# ChassisCab-samd21g.net
KiCad netlist of a schematic drawn in EAGLE
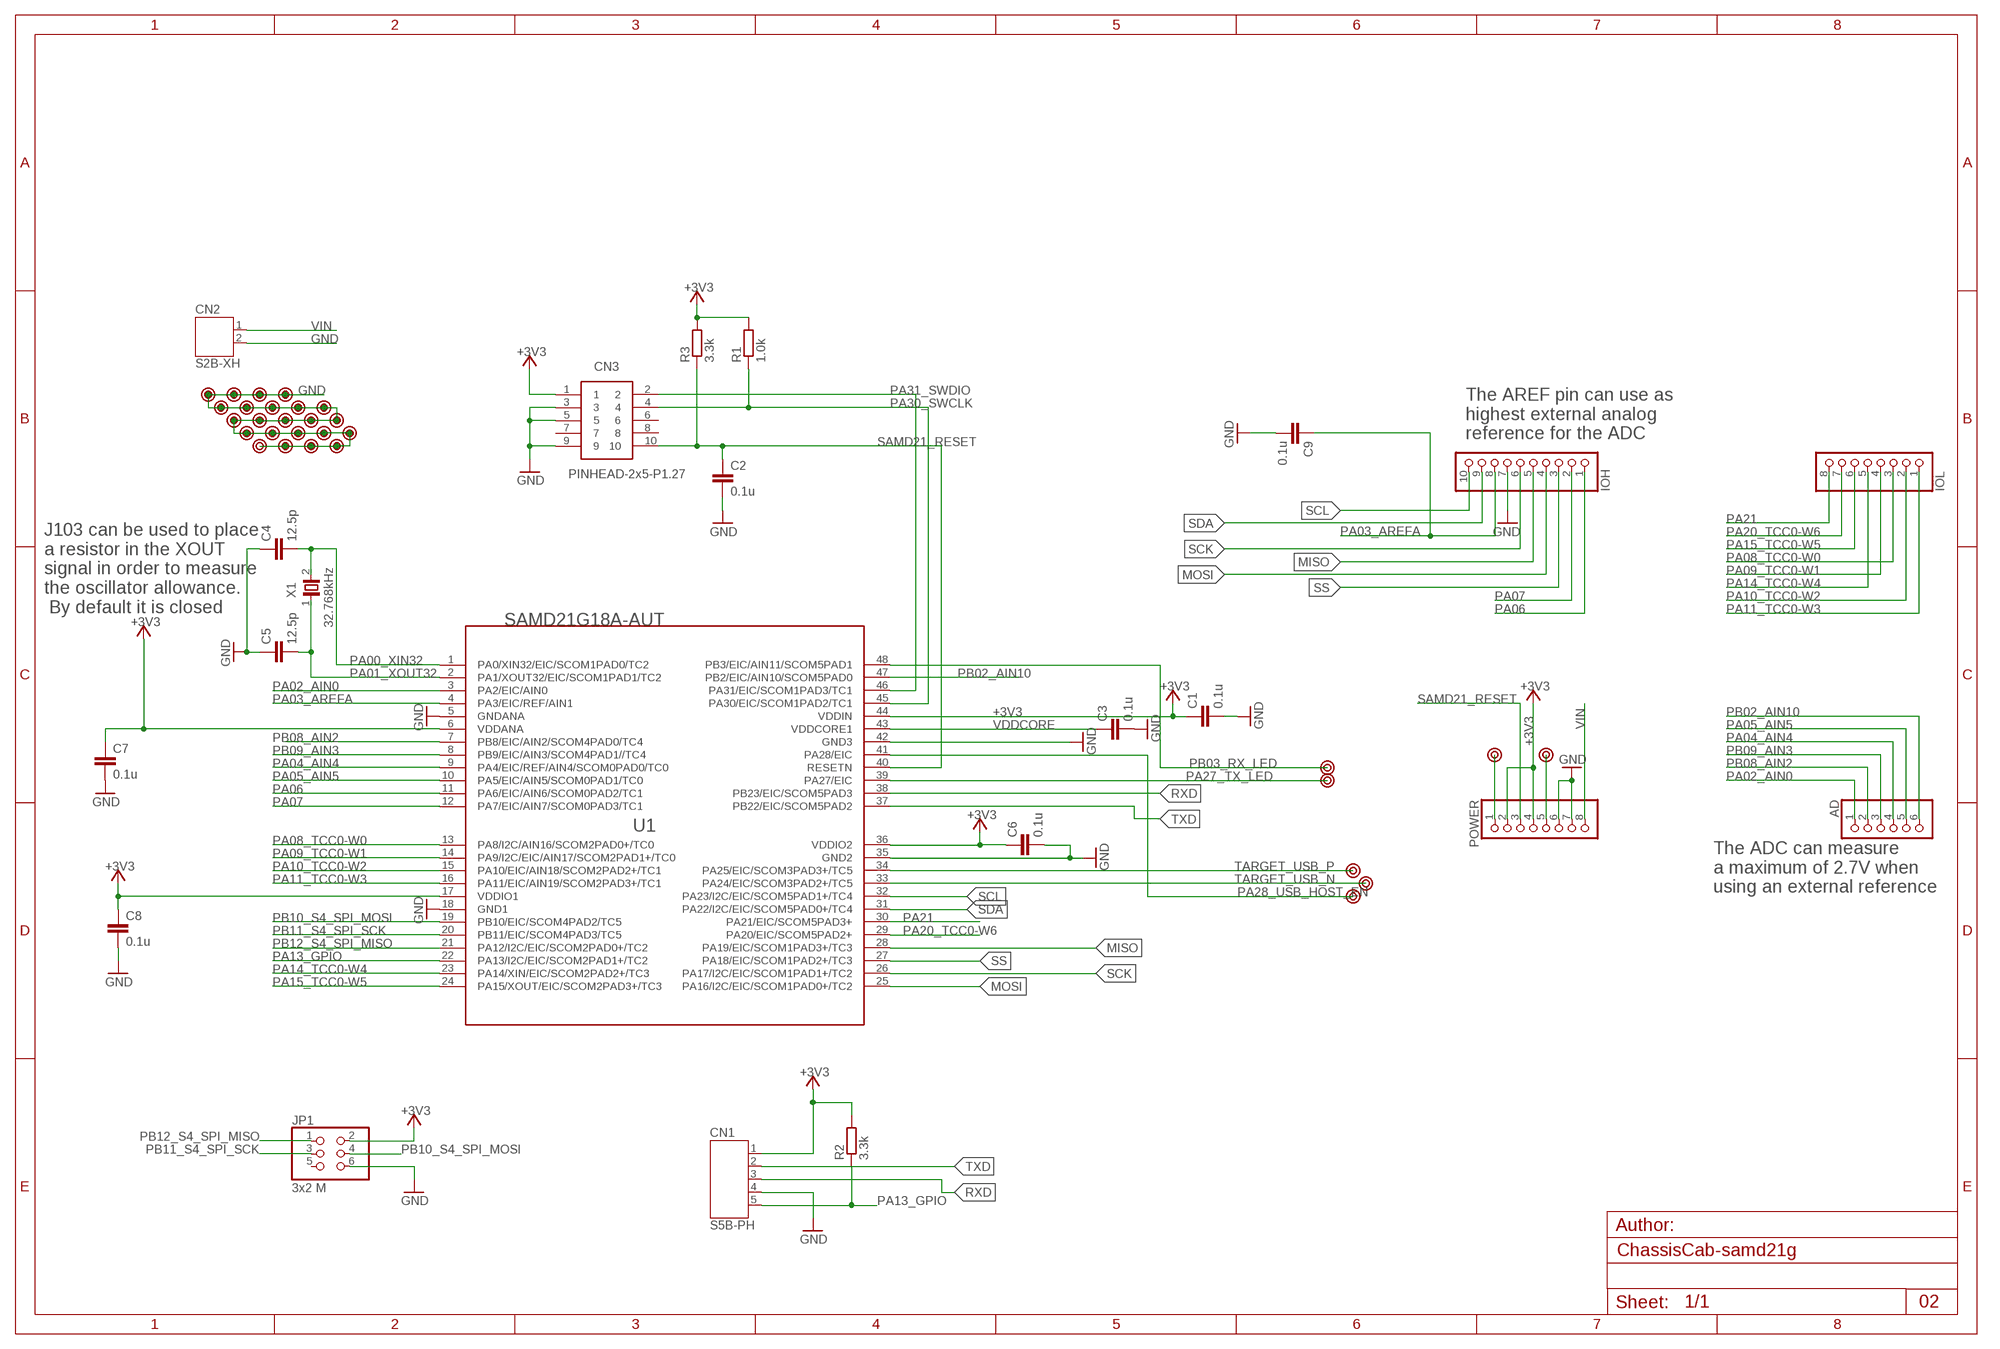
[diagram p0: schematic, sheet 1]

(export (version "E")
  (design (tool "Eeschema 10.0.6"))
  (components
    (comp (ref "AD")
      (value "6x1F-H8.5")
      (footprint "eagle-import:1X06")
      (libsource (lib "eagle-import") (part "PINHD-1X6"))
    )
    (comp (ref "C1")
      (value "0.1u")
      (footprint "eagle-import:C0603")
      (libsource (lib "eagle-import") (part "C-EUC0603"))
    )
    (comp (ref "C2")
      (value "0.1u")
      (footprint "eagle-import:C0603")
      (libsource (lib "eagle-import") (part "C-EUC0603"))
    )
    (comp (ref "C3")
      (value "0.1u")
      (footprint "eagle-import:C0603")
      (libsource (lib "eagle-import") (part "C-EUC0603"))
    )
    (comp (ref "C4")
      (value "12.5p")
      (footprint "eagle-import:C0603")
      (libsource (lib "eagle-import") (part "C-EUC0603"))
    )
    (comp (ref "C5")
      (value "12.5p")
      (footprint "eagle-import:C0603")
      (libsource (lib "eagle-import") (part "C-EUC0603"))
    )
    (comp (ref "C6")
      (value "0.1u")
      (footprint "eagle-import:C0603")
      (libsource (lib "eagle-import") (part "C-EUC0603"))
    )
    (comp (ref "C7")
      (value "0.1u")
      (footprint "eagle-import:C0603")
      (libsource (lib "eagle-import") (part "C-EUC0603"))
    )
    (comp (ref "C8")
      (value "0.1u")
      (footprint "eagle-import:C0603")
      (libsource (lib "eagle-import") (part "C-EUC0603"))
    )
    (comp (ref "C9")
      (value "0.1u")
      (footprint "eagle-import:C0603")
      (libsource (lib "eagle-import") (part "C-EUC0603"))
    )
    (comp (ref "CN1")
      (value "S5B-PH")
      (footprint "eagle-import:S5B-PH")
      (libsource (lib "eagle-import") (part "S5B-PH"))
    )
    (comp (ref "CN2")
      (value "S2B-XH")
      (footprint "eagle-import:S2B-XH")
      (libsource (lib "eagle-import") (part "S2B-XH"))
    )
    (comp (ref "CN3")
      (value "PINHEAD-2x5-P1.27")
      (footprint "eagle-import:SHF-105-01-X-D-SM")
      (libsource (lib "eagle-import") (part "SHF-105-01-X-D-SM"))
    )
    (comp (ref "IOH")
      (value "10x1F-H8.5")
      (footprint "eagle-import:1X10")
      (libsource (lib "eagle-import") (part "PINHD-1X10_ARD"))
    )
    (comp (ref "IOL")
      (value "8x1F-H8.5")
      (footprint "eagle-import:1X08")
      (libsource (lib "eagle-import") (part "PINHD-1X8"))
    )
    (comp (ref "JP1")
      (value "3x2 M")
      (footprint "eagle-import:2X03")
      (libsource (lib "eagle-import") (part "PINHD-2X3"))
    )
    (comp (ref "POWER")
      (value "8x1F-H8.5")
      (footprint "eagle-import:1X08")
      (libsource (lib "eagle-import") (part "PINHD-1X8"))
    )
    (comp (ref "R1")
      (value "1.0k")
      (footprint "eagle-import:R0603")
      (libsource (lib "eagle-import") (part "R-EU_R0603"))
    )
    (comp (ref "R2")
      (value "3.3k")
      (footprint "eagle-import:R0603")
      (libsource (lib "eagle-import") (part "R-EU_R0603"))
    )
    (comp (ref "R3")
      (value "3.3k")
      (footprint "eagle-import:R0603")
      (libsource (lib "eagle-import") (part "R-EU_R0603"))
    )
    (comp (ref "U$1")
      (value "PAD")
      (footprint "eagle-import:PAD")
      (libsource (lib "eagle-import") (part "PAD"))
    )
    (comp (ref "U$2")
      (value "PAD")
      (footprint "eagle-import:PAD")
      (libsource (lib "eagle-import") (part "PAD"))
    )
    (comp (ref "U$3")
      (value "PAD")
      (footprint "eagle-import:PAD")
      (libsource (lib "eagle-import") (part "PAD"))
    )
    (comp (ref "U$4")
      (value "PAD")
      (footprint "eagle-import:PAD")
      (libsource (lib "eagle-import") (part "PAD"))
    )
    (comp (ref "U$6")
      (value "PAD")
      (footprint "eagle-import:PAD")
      (libsource (lib "eagle-import") (part "PAD"))
    )
    (comp (ref "U$7")
      (value "PAD")
      (footprint "eagle-import:PAD")
      (libsource (lib "eagle-import") (part "PAD"))
    )
    (comp (ref "U$8")
      (value "PAD")
      (footprint "eagle-import:PAD")
      (libsource (lib "eagle-import") (part "PAD"))
    )
    (comp (ref "U$9")
      (value "PAD")
      (footprint "eagle-import:PAD")
      (libsource (lib "eagle-import") (part "PAD"))
    )
    (comp (ref "U$10")
      (value "PAD")
      (footprint "eagle-import:PAD")
      (libsource (lib "eagle-import") (part "PAD"))
    )
    (comp (ref "U$11")
      (value "PAD")
      (footprint "eagle-import:PAD")
      (libsource (lib "eagle-import") (part "PAD"))
    )
    (comp (ref "U$12")
      (value "PAD")
      (footprint "eagle-import:PAD")
      (libsource (lib "eagle-import") (part "PAD"))
    )
    (comp (ref "U$13")
      (value "PAD")
      (footprint "eagle-import:PAD")
      (libsource (lib "eagle-import") (part "PAD"))
    )
    (comp (ref "U$14")
      (value "PAD")
      (footprint "eagle-import:PAD")
      (libsource (lib "eagle-import") (part "PAD"))
    )
    (comp (ref "U$15")
      (value "PAD")
      (footprint "eagle-import:PAD")
      (libsource (lib "eagle-import") (part "PAD"))
    )
    (comp (ref "U$16")
      (value "PAD")
      (footprint "eagle-import:PAD")
      (libsource (lib "eagle-import") (part "PAD"))
    )
    (comp (ref "U$17")
      (value "PAD")
      (footprint "eagle-import:PAD")
      (libsource (lib "eagle-import") (part "PAD"))
    )
    (comp (ref "U$18")
      (value "PAD")
      (footprint "eagle-import:PAD")
      (libsource (lib "eagle-import") (part "PAD"))
    )
    (comp (ref "U$19")
      (value "PAD")
      (footprint "eagle-import:PAD")
      (libsource (lib "eagle-import") (part "PAD"))
    )
    (comp (ref "U$20")
      (value "PAD")
      (footprint "eagle-import:PAD")
      (libsource (lib "eagle-import") (part "PAD"))
    )
    (comp (ref "U$21")
      (value "PAD")
      (footprint "eagle-import:PAD")
      (libsource (lib "eagle-import") (part "PAD"))
    )
    (comp (ref "U$22")
      (value "PAD")
      (footprint "eagle-import:PAD")
      (libsource (lib "eagle-import") (part "PAD"))
    )
    (comp (ref "U$23")
      (value "PAD")
      (footprint "eagle-import:PAD")
      (libsource (lib "eagle-import") (part "PAD"))
    )
    (comp (ref "U$24")
      (value "PAD")
      (footprint "eagle-import:PAD")
      (libsource (lib "eagle-import") (part "PAD"))
    )
    (comp (ref "U$25")
      (value "PAD")
      (footprint "eagle-import:PAD")
      (libsource (lib "eagle-import") (part "PAD"))
    )
    (comp (ref "U$26")
      (value "PAD")
      (footprint "eagle-import:PAD")
      (libsource (lib "eagle-import") (part "PAD"))
    )
    (comp (ref "U$27")
      (value "PAD")
      (footprint "eagle-import:PAD")
      (libsource (lib "eagle-import") (part "PAD"))
    )
    (comp (ref "U$28")
      (value "PAD")
      (footprint "eagle-import:PAD")
      (libsource (lib "eagle-import") (part "PAD"))
    )
    (comp (ref "U$29")
      (value "PAD")
      (footprint "eagle-import:PAD")
      (libsource (lib "eagle-import") (part "PAD"))
    )
    (comp (ref "U$30")
      (value "PAD")
      (footprint "eagle-import:PAD")
      (libsource (lib "eagle-import") (part "PAD"))
    )
    (comp (ref "U$31")
      (value "PAD")
      (footprint "eagle-import:PAD")
      (libsource (lib "eagle-import") (part "PAD"))
    )
    (comp (ref "U1")
      (value "SAMD21G18A-AUT")
      (footprint "eagle-import:TQFP48")
      (libsource (lib "eagle-import") (part "SAMD21G18A"))
    )
    (comp (ref "X1")
      (value "32.768kHz")
      (footprint "eagle-import:FC-135")
      (libsource (lib "eagle-import") (part "FC-135"))
    )
  )
  (nets
    (net (code "1") (name "+3V3") (class "Default")
      (node (ref "C1") (pin "1") (pinfunction "1_1") (pintype "passive"))
      (node (ref "C6") (pin "1") (pinfunction "1_1") (pintype "passive"))
      (node (ref "C7") (pin "1") (pinfunction "1_1") (pintype "passive"))
      (node (ref "C8") (pin "1") (pinfunction "1_1") (pintype "passive"))
      (node (ref "CN1") (pin "1") (pinfunction "1_1") (pintype "passive"))
      (node (ref "CN3") (pin "1") (pinfunction "1_1") (pintype "bidirectional"))
      (node (ref "JP1") (pin "2") (pinfunction "2_2") (pintype "passive"))
      (node (ref "POWER") (pin "2") (pinfunction "2_2") (pintype "passive"))
      (node (ref "POWER") (pin "4") (pinfunction "4_4") (pintype "passive"))
      (node (ref "R1") (pin "2") (pinfunction "2_2") (pintype "passive"))
      (node (ref "R2") (pin "2") (pinfunction "2_2") (pintype "passive"))
      (node (ref "R3") (pin "2") (pinfunction "2_2") (pintype "passive"))
      (node (ref "U1") (pin "17") (pinfunction "VDDIO1_17") (pintype "power_in"))
      (node (ref "U1") (pin "36") (pinfunction "VDDIO2_36") (pintype "power_in"))
      (node (ref "U1") (pin "44") (pinfunction "VDDIN_44") (pintype "power_in"))
      (node (ref "U1") (pin "6") (pinfunction "VDDANA_6") (pintype "power_in"))
    )
    (net (code "2") (name "/PA00_XIN32") (class "Default")
      (node (ref "C4") (pin "2") (pinfunction "2_2") (pintype "passive"))
      (node (ref "U1") (pin "1") (pinfunction "PA0/XIN32/EIC/SCOM1PAD0/TC2_1") (pintype "bidirectional"))
      (node (ref "X1") (pin "2") (pinfunction "2_2") (pintype "passive"))
    )
    (net (code "3") (name "/PA01_XOUT32") (class "Default")
      (node (ref "C5") (pin "2") (pinfunction "2_2") (pintype "passive"))
      (node (ref "U1") (pin "2") (pinfunction "PA1/XOUT32/EIC/SCOM1PAD1/TC2_2") (pintype "bidirectional"))
      (node (ref "X1") (pin "1") (pinfunction "1_1") (pintype "passive"))
    )
    (net (code "4") (name "/PA02_AIN0") (class "Default")
      (node (ref "AD") (pin "1") (pinfunction "1_1") (pintype "passive"))
      (node (ref "U1") (pin "3") (pinfunction "PA2/EIC/AIN0_3") (pintype "bidirectional"))
    )
    (net (code "5") (name "/PA03_AREFA") (class "Default")
      (node (ref "C9") (pin "1") (pinfunction "1_1") (pintype "passive"))
      (node (ref "IOH") (pin "8") (pinfunction "8_8") (pintype "passive"))
      (node (ref "U1") (pin "4") (pinfunction "PA3/EIC/REF/AIN1_4") (pintype "bidirectional"))
    )
    (net (code "6") (name "/PA04_AIN4") (class "Default")
      (node (ref "AD") (pin "4") (pinfunction "4_4") (pintype "passive"))
      (node (ref "U1") (pin "9") (pinfunction "PA4/EIC/REF/AIN4/SCOM0PAD0/TC0_9") (pintype "bidirectional"))
    )
    (net (code "7") (name "/PA05_AIN5") (class "Default")
      (node (ref "AD") (pin "5") (pinfunction "5_5") (pintype "passive"))
      (node (ref "U1") (pin "10") (pinfunction "PA5/EIC/AIN5/SCOM0PAD1/TC0_10") (pintype "bidirectional"))
    )
    (net (code "8") (name "/PA06") (class "Default")
      (node (ref "IOH") (pin "1") (pinfunction "1_1") (pintype "passive"))
      (node (ref "U1") (pin "11") (pinfunction "PA6/EIC/AIN6/SCOM0PAD2/TC1_11") (pintype "bidirectional"))
    )
    (net (code "9") (name "/PA07") (class "Default")
      (node (ref "IOH") (pin "2") (pinfunction "2_2") (pintype "passive"))
      (node (ref "U1") (pin "12") (pinfunction "PA7/EIC/AIN7/SCOM0PAD3/TC1_12") (pintype "bidirectional"))
    )
    (net (code "10") (name "/PA08_TCC0-W0") (class "Default")
      (node (ref "IOL") (pin "3") (pinfunction "3_3") (pintype "passive"))
      (node (ref "U1") (pin "13") (pinfunction "PA8/I2C/AIN16/SCOM2PAD0+/TC0_13") (pintype "bidirectional"))
    )
    (net (code "11") (name "/PA09_TCC0-W1") (class "Default")
      (node (ref "IOL") (pin "4") (pinfunction "4_4") (pintype "passive"))
      (node (ref "U1") (pin "14") (pinfunction "PA9/I2C/EIC/AIN17/SCOM2PAD1+/TC0_14") (pintype "bidirectional"))
    )
    (net (code "12") (name "/PA10_TCC0-W2") (class "Default")
      (node (ref "IOL") (pin "2") (pinfunction "2_2") (pintype "passive"))
      (node (ref "U1") (pin "15") (pinfunction "PA10/EIC/AIN18/SCOM2PAD2+/TC1_15") (pintype "bidirectional"))
    )
    (net (code "13") (name "/PA11_TCC0-W3") (class "Default")
      (node (ref "IOL") (pin "1") (pinfunction "1_1") (pintype "passive"))
      (node (ref "U1") (pin "16") (pinfunction "PA11/EIC/AIN19/SCOM2PAD3+/TC1_16") (pintype "bidirectional"))
    )
    (net (code "14") (name "/PA13_GPIO") (class "Default")
      (node (ref "CN1") (pin "5") (pinfunction "5_5") (pintype "passive"))
      (node (ref "R2") (pin "1") (pinfunction "1_1") (pintype "passive"))
      (node (ref "U1") (pin "22") (pinfunction "PA13/I2C/EIC/SCOM2PAD1+/TC2_22") (pintype "bidirectional"))
    )
    (net (code "15") (name "/PA14_TCC0-W4") (class "Default")
      (node (ref "IOL") (pin "5") (pinfunction "5_5") (pintype "passive"))
      (node (ref "U1") (pin "23") (pinfunction "PA14/XIN/EIC/SCOM2PAD2+/TC3_23") (pintype "bidirectional"))
    )
    (net (code "16") (name "/PA15_TCC0-W5") (class "Default")
      (node (ref "IOL") (pin "6") (pinfunction "6_6") (pintype "passive"))
      (node (ref "U1") (pin "24") (pinfunction "PA15/XOUT/EIC/SCOM2PAD3+/TC3_24") (pintype "bidirectional"))
    )
    (net (code "17") (name "/PA20_TCC0-W6") (class "Default")
      (node (ref "IOL") (pin "7") (pinfunction "7_7") (pintype "passive"))
      (node (ref "U1") (pin "29") (pinfunction "PA20/EIC/SCOM5PAD2+_29") (pintype "bidirectional"))
    )
    (net (code "18") (name "/PA21") (class "Default")
      (node (ref "IOL") (pin "8") (pinfunction "8_8") (pintype "passive"))
      (node (ref "U1") (pin "30") (pinfunction "PA21/EIC/SCOM5PAD3+_30") (pintype "bidirectional"))
    )
    (net (code "19") (name "/PA27_TX_LED") (class "Default")
      (node (ref "U$4") (pin "1") (pinfunction "1_1") (pintype "passive"))
      (node (ref "U1") (pin "39") (pinfunction "PA27/EIC_39") (pintype "bidirectional"))
    )
    (net (code "20") (name "/PA28_USB_HOST_EN") (class "Default")
      (node (ref "U$3") (pin "1") (pinfunction "1_1") (pintype "passive"))
      (node (ref "U1") (pin "41") (pinfunction "PA28/EIC_41") (pintype "bidirectional"))
    )
    (net (code "21") (name "/PA30_SWCLK") (class "Default")
      (node (ref "CN3") (pin "4") (pinfunction "4_4") (pintype "bidirectional"))
      (node (ref "R1") (pin "1") (pinfunction "1_1") (pintype "passive"))
      (node (ref "U1") (pin "45") (pinfunction "PA30/EIC/SCOM1PAD2/TC1_45") (pintype "bidirectional"))
    )
    (net (code "22") (name "/PA31_SWDIO") (class "Default")
      (node (ref "CN3") (pin "2") (pinfunction "2_2") (pintype "bidirectional"))
      (node (ref "U1") (pin "46") (pinfunction "PA31/EIC/SCOM1PAD3/TC1_46") (pintype "bidirectional"))
    )
    (net (code "23") (name "/PB02_AIN10") (class "Default")
      (node (ref "AD") (pin "6") (pinfunction "6_6") (pintype "passive"))
      (node (ref "U1") (pin "47") (pinfunction "PB2/EIC/AIN10/SCOM5PAD0_47") (pintype "bidirectional"))
    )
    (net (code "24") (name "/PB03_RX_LED") (class "Default")
      (node (ref "U$1") (pin "1") (pinfunction "1_1") (pintype "passive"))
      (node (ref "U1") (pin "48") (pinfunction "PB3/EIC/AIN11/SCOM5PAD1_48") (pintype "bidirectional"))
    )
    (net (code "25") (name "/PB08_AIN2") (class "Default")
      (node (ref "AD") (pin "2") (pinfunction "2_2") (pintype "passive"))
      (node (ref "U1") (pin "7") (pinfunction "PB8/EIC/AIN2/SCOM4PAD0/TC4_7") (pintype "bidirectional"))
    )
    (net (code "26") (name "/PB09_AIN3") (class "Default")
      (node (ref "AD") (pin "3") (pinfunction "3_3") (pintype "passive"))
      (node (ref "U1") (pin "8") (pinfunction "PB9/EIC/AIN3/SCOM4PAD1//TC4_8") (pintype "bidirectional"))
    )
    (net (code "27") (name "/PB10_S4_SPI_MOSI") (class "Default")
      (node (ref "JP1") (pin "4") (pinfunction "4_4") (pintype "passive"))
      (node (ref "U1") (pin "19") (pinfunction "PB10/EIC/SCOM4PAD2/TC5_19") (pintype "bidirectional"))
    )
    (net (code "28") (name "/PB11_S4_SPI_SCK") (class "Default")
      (node (ref "JP1") (pin "3") (pinfunction "3_3") (pintype "passive"))
      (node (ref "U1") (pin "20") (pinfunction "PB11/EIC/SCOM4PAD3/TC5_20") (pintype "bidirectional"))
    )
    (net (code "29") (name "/PB12_S4_SPI_MISO") (class "Default")
      (node (ref "JP1") (pin "1") (pinfunction "1_1") (pintype "passive"))
      (node (ref "U1") (pin "21") (pinfunction "PA12/I2C/EIC/SCOM2PAD0+/TC2_21") (pintype "bidirectional"))
    )
    (net (code "30") (name "/SAMD21_RESET") (class "Default")
      (node (ref "C2") (pin "1") (pinfunction "1_1") (pintype "passive"))
      (node (ref "CN3") (pin "10") (pinfunction "10_10") (pintype "bidirectional"))
      (node (ref "POWER") (pin "3") (pinfunction "3_3") (pintype "passive"))
      (node (ref "R3") (pin "1") (pinfunction "1_1") (pintype "passive"))
      (node (ref "U1") (pin "40") (pinfunction "RESETN_40") (pintype "bidirectional"))
    )
    (net (code "31") (name "/TARGET_USB_N") (class "Default")
      (node (ref "U$7") (pin "1") (pinfunction "1_1") (pintype "passive"))
      (node (ref "U1") (pin "33") (pinfunction "PA24/EIC/SCOM3PAD2+/TC5_33") (pintype "bidirectional"))
    )
    (net (code "32") (name "/TARGET_USB_P") (class "Default")
      (node (ref "U$6") (pin "1") (pinfunction "1_1") (pintype "passive"))
      (node (ref "U1") (pin "34") (pinfunction "PA25/EIC/SCOM3PAD3+/TC5_34") (pintype "bidirectional"))
    )
    (net (code "33") (name "/VDDCORE") (class "Default")
      (node (ref "C3") (pin "1") (pinfunction "1_1") (pintype "passive"))
      (node (ref "U1") (pin "43") (pinfunction "VDDCORE1_43") (pintype "input"))
    )
    (net (code "34") (name "/VIN") (class "Default")
      (node (ref "CN2") (pin "1") (pinfunction "1_1") (pintype "passive"))
      (node (ref "POWER") (pin "8") (pinfunction "8_8") (pintype "passive"))
    )
    (net (code "35") (name "GND") (class "Default")
      (node (ref "C1") (pin "2") (pinfunction "2_2") (pintype "passive"))
      (node (ref "C2") (pin "2") (pinfunction "2_2") (pintype "passive"))
      (node (ref "C3") (pin "2") (pinfunction "2_2") (pintype "passive"))
      (node (ref "C4") (pin "1") (pinfunction "1_1") (pintype "passive"))
      (node (ref "C5") (pin "1") (pinfunction "1_1") (pintype "passive"))
      (node (ref "C6") (pin "2") (pinfunction "2_2") (pintype "passive"))
      (node (ref "C7") (pin "2") (pinfunction "2_2") (pintype "passive"))
      (node (ref "C8") (pin "2") (pinfunction "2_2") (pintype "passive"))
      (node (ref "C9") (pin "2") (pinfunction "2_2") (pintype "passive"))
      (node (ref "CN1") (pin "4") (pinfunction "4_4") (pintype "passive"))
      (node (ref "CN2") (pin "2") (pinfunction "2_2") (pintype "passive"))
      (node (ref "CN3") (pin "3") (pinfunction "3_3") (pintype "bidirectional"))
      (node (ref "CN3") (pin "5") (pinfunction "5_5") (pintype "bidirectional"))
      (node (ref "CN3") (pin "9") (pinfunction "9_9") (pintype "bidirectional"))
      (node (ref "IOH") (pin "7") (pinfunction "7_7") (pintype "passive"))
      (node (ref "JP1") (pin "6") (pinfunction "6_6") (pintype "passive"))
      (node (ref "POWER") (pin "6") (pinfunction "6_6") (pintype "passive"))
      (node (ref "POWER") (pin "7") (pinfunction "7_7") (pintype "passive"))
      (node (ref "U$10") (pin "1") (pinfunction "1_1") (pintype "passive"))
      (node (ref "U$11") (pin "1") (pinfunction "1_1") (pintype "passive"))
      (node (ref "U$12") (pin "1") (pinfunction "1_1") (pintype "passive"))
      (node (ref "U$13") (pin "1") (pinfunction "1_1") (pintype "passive"))
      (node (ref "U$14") (pin "1") (pinfunction "1_1") (pintype "passive"))
      (node (ref "U$15") (pin "1") (pinfunction "1_1") (pintype "passive"))
      (node (ref "U$16") (pin "1") (pinfunction "1_1") (pintype "passive"))
      (node (ref "U$17") (pin "1") (pinfunction "1_1") (pintype "passive"))
      (node (ref "U$18") (pin "1") (pinfunction "1_1") (pintype "passive"))
      (node (ref "U$19") (pin "1") (pinfunction "1_1") (pintype "passive"))
      (node (ref "U$2") (pin "1") (pinfunction "1_1") (pintype "passive"))
      (node (ref "U$20") (pin "1") (pinfunction "1_1") (pintype "passive"))
      (node (ref "U$21") (pin "1") (pinfunction "1_1") (pintype "passive"))
      (node (ref "U$22") (pin "1") (pinfunction "1_1") (pintype "passive"))
      (node (ref "U$23") (pin "1") (pinfunction "1_1") (pintype "passive"))
      (node (ref "U$24") (pin "1") (pinfunction "1_1") (pintype "passive"))
      (node (ref "U$25") (pin "1") (pinfunction "1_1") (pintype "passive"))
      (node (ref "U$26") (pin "1") (pinfunction "1_1") (pintype "passive"))
      (node (ref "U$27") (pin "1") (pinfunction "1_1") (pintype "passive"))
      (node (ref "U$28") (pin "1") (pinfunction "1_1") (pintype "passive"))
      (node (ref "U$31") (pin "1") (pinfunction "1_1") (pintype "passive"))
      (node (ref "U$8") (pin "1") (pinfunction "1_1") (pintype "passive"))
      (node (ref "U$9") (pin "1") (pinfunction "1_1") (pintype "passive"))
      (node (ref "U1") (pin "18") (pinfunction "GND1_18") (pintype "power_in"))
      (node (ref "U1") (pin "35") (pinfunction "GND2_35") (pintype "power_in"))
      (node (ref "U1") (pin "42") (pinfunction "GND3_42") (pintype "power_in"))
      (node (ref "U1") (pin "5") (pinfunction "GNDANA_5") (pintype "power_in"))
    )
    (net (code "36") (name "MISO") (class "Default")
      (node (ref "IOH") (pin "5") (pinfunction "5_5") (pintype "passive"))
      (node (ref "U1") (pin "28") (pinfunction "PA19/EIC/SCOM1PAD3+/TC3_28") (pintype "bidirectional"))
    )
    (net (code "37") (name "MOSI") (class "Default")
      (node (ref "IOH") (pin "4") (pinfunction "4_4") (pintype "passive"))
      (node (ref "U1") (pin "25") (pinfunction "PA16/I2C/EIC/SCOM1PAD0+/TC2_25") (pintype "bidirectional"))
    )
    (net (code "38") (name "Net-(POWER-Pad1)") (class "Default")
      (node (ref "POWER") (pin "1") (pinfunction "1_1") (pintype "passive"))
      (node (ref "U$29") (pin "1") (pinfunction "1_1") (pintype "passive"))
    )
    (net (code "39") (name "Net-(POWER-Pad5)") (class "Default")
      (node (ref "POWER") (pin "5") (pinfunction "5_5") (pintype "passive"))
      (node (ref "U$30") (pin "1") (pinfunction "1_1") (pintype "passive"))
    )
    (net (code "40") (name "RXD") (class "Default")
      (node (ref "CN1") (pin "3") (pinfunction "3_3") (pintype "passive"))
      (node (ref "U1") (pin "38") (pinfunction "PB23/EIC/SCOM5PAD3_38") (pintype "bidirectional"))
    )
    (net (code "41") (name "SCK") (class "Default")
      (node (ref "IOH") (pin "6") (pinfunction "6_6") (pintype "passive"))
      (node (ref "U1") (pin "26") (pinfunction "PA17/I2C/EIC/SCOM1PAD1+/TC2_26") (pintype "bidirectional"))
    )
    (net (code "42") (name "SCL") (class "Default")
      (node (ref "IOH") (pin "10") (pinfunction "10_10") (pintype "passive"))
      (node (ref "U1") (pin "32") (pinfunction "PA23/I2C/EIC/SCOM5PAD1+/TC4_32") (pintype "bidirectional"))
    )
    (net (code "43") (name "SDA") (class "Default")
      (node (ref "IOH") (pin "9") (pinfunction "9_9") (pintype "passive"))
      (node (ref "U1") (pin "31") (pinfunction "PA22/I2C/EIC/SCOM5PAD0+/TC4_31") (pintype "bidirectional"))
    )
    (net (code "44") (name "SS") (class "Default")
      (node (ref "IOH") (pin "3") (pinfunction "3_3") (pintype "passive"))
      (node (ref "U1") (pin "27") (pinfunction "PA18/EIC/SCOM1PAD2+/TC3_27") (pintype "bidirectional"))
    )
    (net (code "45") (name "TXD") (class "Default")
      (node (ref "CN1") (pin "2") (pinfunction "2_2") (pintype "passive"))
      (node (ref "U1") (pin "37") (pinfunction "PB22/EIC/SCOM5PAD2_37") (pintype "bidirectional"))
    )
    (net (code "46") (name "unconnected-(CN3-Pad6)") (class "Default")
      (node (ref "CN3") (pin "6") (pinfunction "6_6") (pintype "bidirectional"))
    )
    (net (code "47") (name "unconnected-(CN3-Pad7)") (class "Default")
      (node (ref "CN3") (pin "7") (pinfunction "7_7") (pintype "bidirectional"))
    )
    (net (code "48") (name "unconnected-(CN3-Pad8)") (class "Default")
      (node (ref "CN3") (pin "8") (pinfunction "8_8") (pintype "bidirectional"))
    )
    (net (code "49") (name "unconnected-(JP1-Pad5)") (class "Default")
      (node (ref "JP1") (pin "5") (pinfunction "5_5") (pintype "passive"))
    )
  )
)
